# stm32c8t6.net
KiCad netlist of a schematic drawn in Altium Designer
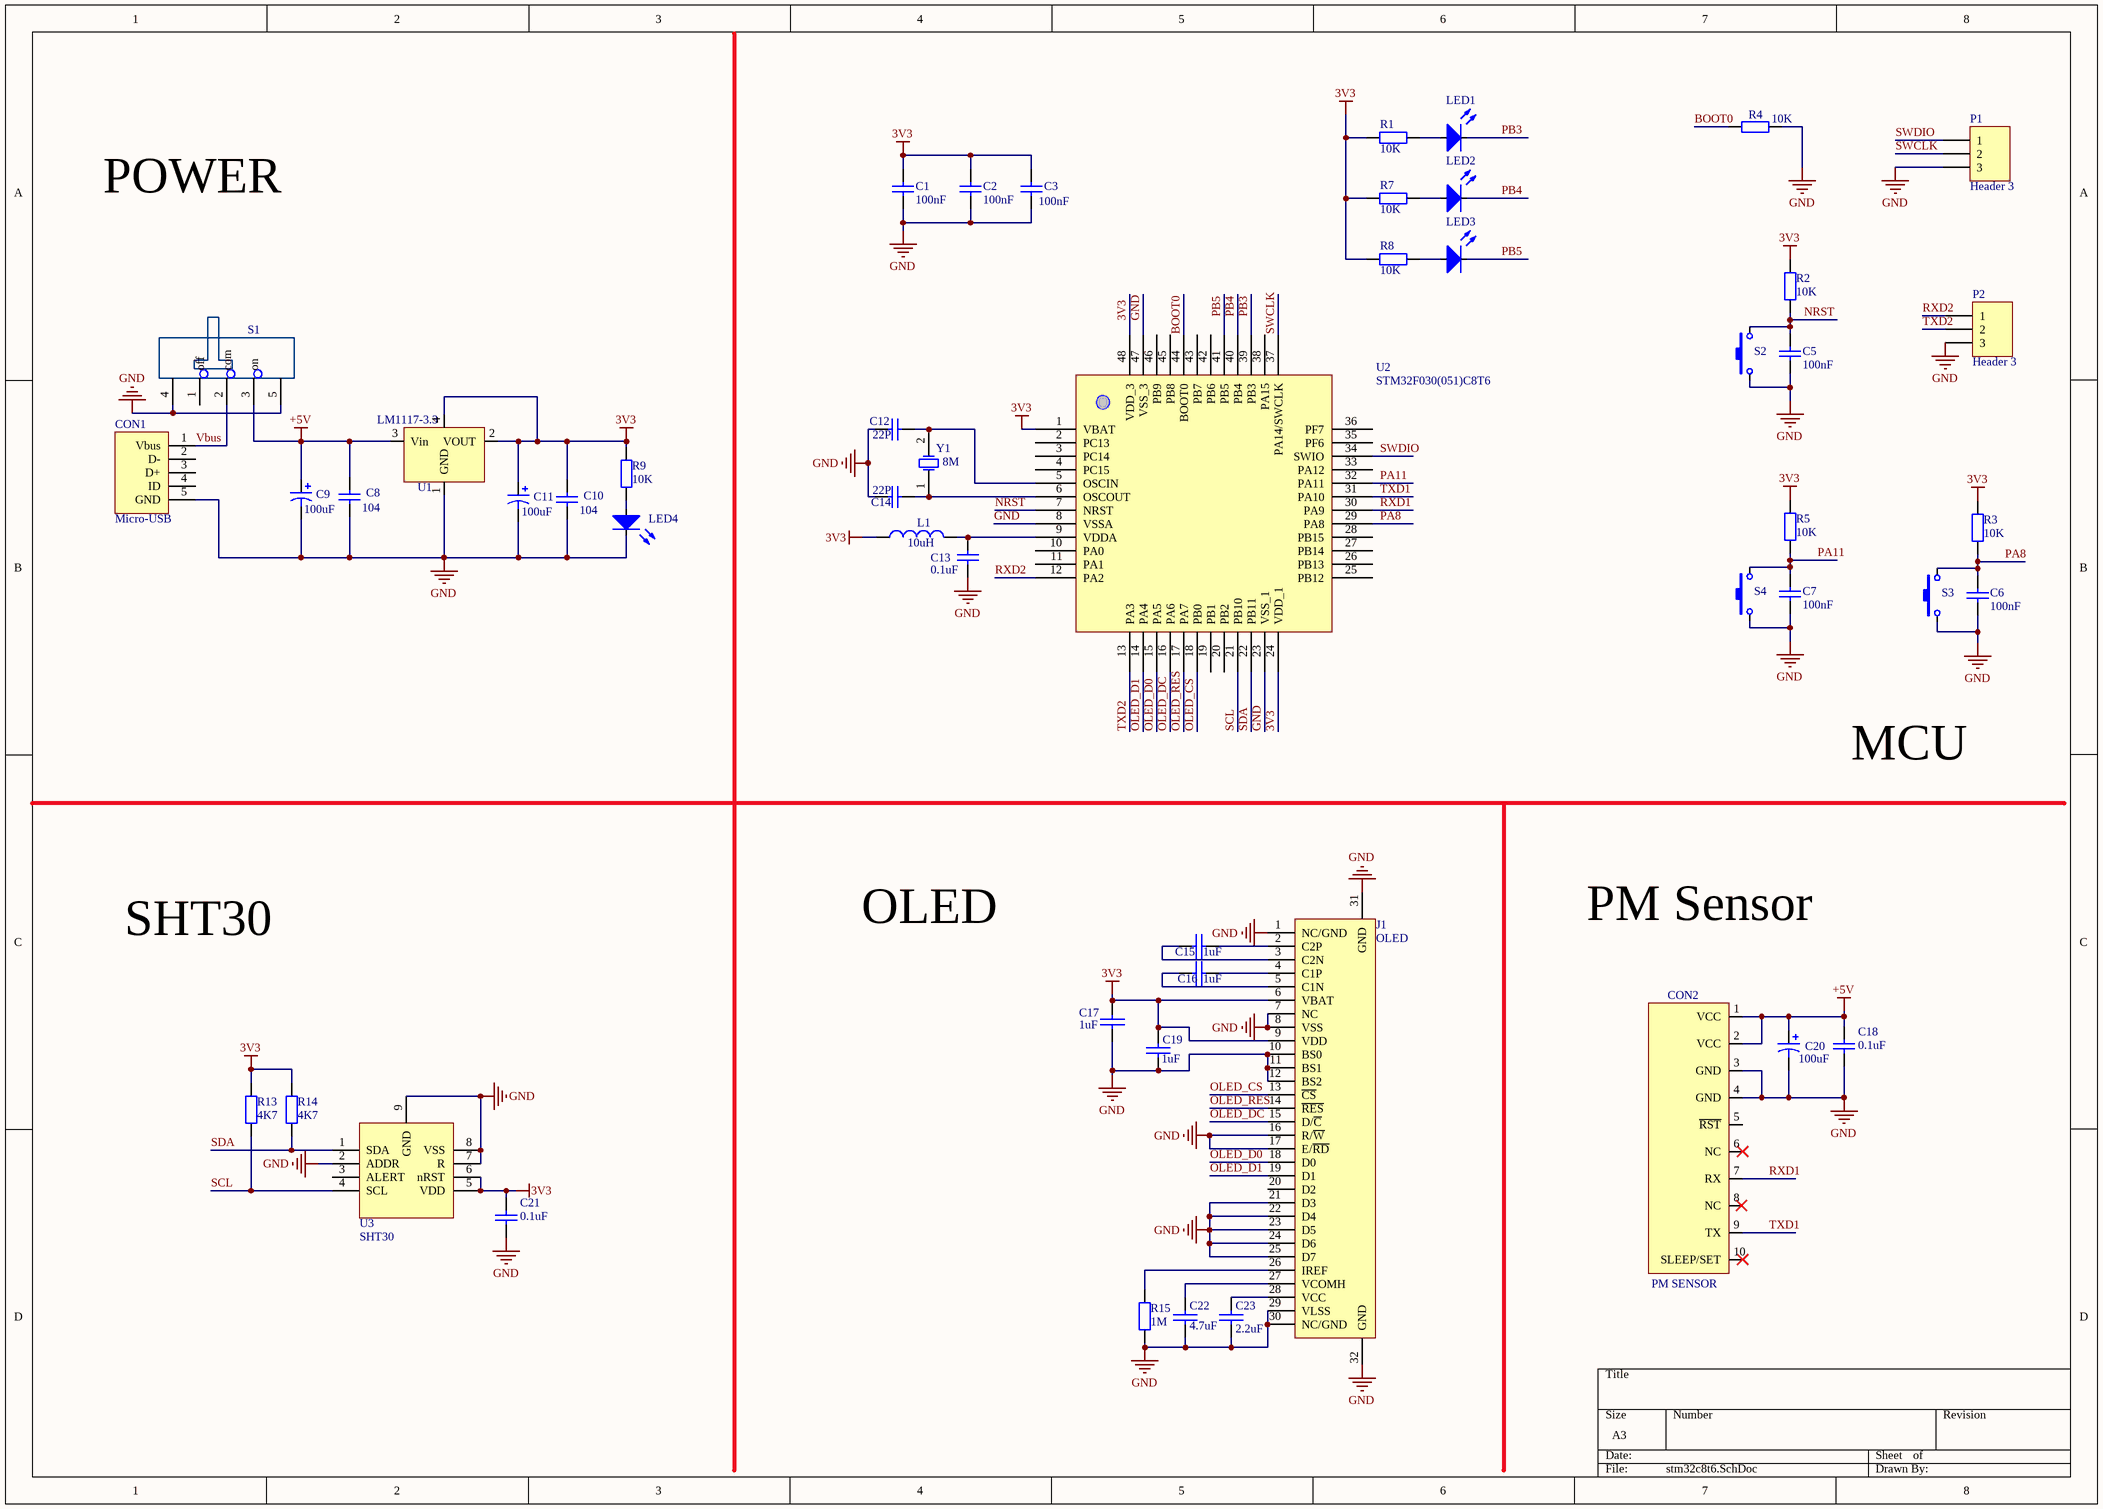
[diagram p0: stm32c8t6.SchDoc]

(export (version "E")
  (design (tool "Eeschema 10.0.6"))
  (components
    (comp (ref "C1")
      (value "100nF")
      (footprint "0603BY")
      (description "Capacitor")
      (fields (field (name "Comment") "Cap") (field (name "PUBLISHER") "Altium Limited"))
      (libsource (lib "stm32c8t6") (part "Cap"))
    )
    (comp (ref "C2")
      (value "100nF")
      (footprint "0603BY")
      (description "Capacitor")
      (fields (field (name "Comment") "Cap") (field (name "PUBLISHER") "Altium Limited"))
      (libsource (lib "stm32c8t6") (part "Cap"))
    )
    (comp (ref "C3")
      (value "100nF")
      (footprint "0603BY")
      (description "Capacitor")
      (fields (field (name "Comment") "Cap") (field (name "PUBLISHER") "Altium Limited"))
      (libsource (lib "stm32c8t6") (part "Cap"))
    )
    (comp (ref "C5")
      (value "100nF")
      (footprint "0603BY")
      (description "Capacitor")
      (fields (field (name "Comment") "Cap") (field (name "PUBLISHER") "Altium Limited"))
      (libsource (lib "stm32c8t6") (part "Cap"))
    )
    (comp (ref "C6")
      (value "100nF")
      (footprint "0603BY")
      (description "Capacitor")
      (fields (field (name "Comment") "Cap") (field (name "PUBLISHER") "Altium Limited"))
      (libsource (lib "stm32c8t6") (part "Cap"))
    )
    (comp (ref "C7")
      (value "100nF")
      (footprint "0603BY")
      (description "Capacitor")
      (fields (field (name "Comment") "Cap") (field (name "PUBLISHER") "Altium Limited"))
      (libsource (lib "stm32c8t6") (part "Cap"))
    )
    (comp (ref "C8")
      (value "104")
      (footprint "0603BY")
      (description "Capacitor")
      (fields (field (name "Comment") "100nF") (field (name "PUBLISHER") "Altium Limited"))
      (libsource (lib "Miscellaneous Devices") (part "Cap"))
    )
    (comp (ref "C9")
      (value "100uF")
      (footprint "C T - TAJB")
      (description "Polarized Capacitor (Radial)")
      (fields (field (name "Comment") "100uF/35V") (field (name "PUBLISHER") "Altium Limited"))
      (libsource (lib "Miscellaneous Devices") (part "Cap Pol1"))
    )
    (comp (ref "C10")
      (value "104")
      (footprint "0603BY")
      (description "Capacitor")
      (fields (field (name "Comment") "100nF") (field (name "PUBLISHER") "Altium Limited"))
      (libsource (lib "Miscellaneous Devices") (part "Cap"))
    )
    (comp (ref "C11")
      (value "100uF")
      (footprint "C T - TAJB")
      (description "Polarized Capacitor (Radial)")
      (fields (field (name "Comment") "100uF/35V") (field (name "PUBLISHER") "Altium Limited"))
      (libsource (lib "Miscellaneous Devices") (part "Cap Pol1"))
    )
    (comp (ref "C12")
      (value "22P")
      (footprint "0603BY")
      (description "Capacitor")
      (fields (field (name "Comment") "Cap") (field (name "PUBLISHER") "Altium Limited"))
      (libsource (lib "stm32c8t6") (part "Cap"))
    )
    (comp (ref "C13")
      (value "0.1uF")
      (footprint "0603BY")
      (description "Capacitor")
      (fields (field (name "Comment") "100nF") (field (name "PUBLISHER") "Altium Limited"))
      (libsource (lib "Miscellaneous Devices") (part "Cap"))
    )
    (comp (ref "C14")
      (value "22P")
      (footprint "0603BY")
      (description "Capacitor")
      (fields (field (name "Comment") "Cap") (field (name "PUBLISHER") "Altium Limited"))
      (libsource (lib "stm32c8t6") (part "Cap"))
    )
    (comp (ref "C15")
      (value "1uF")
      (footprint "0603BY")
      (description "Capacitor")
      (libsource (lib "*") (part "CAP"))
    )
    (comp (ref "C16")
      (value "1uF")
      (footprint "0603BY")
      (description "Capacitor")
      (libsource (lib "*") (part "CAP"))
    )
    (comp (ref "C17")
      (value "1uF")
      (footprint "0603BY")
      (description "Capacitor")
      (libsource (lib "*") (part "CAP"))
    )
    (comp (ref "C18")
      (value "0.1uF")
      (footprint "0603BY")
      (description "Capacitor")
      (fields (field (name "Comment") "100nF") (field (name "PUBLISHER") "Altium Limited"))
      (libsource (lib "Miscellaneous Devices") (part "Cap"))
    )
    (comp (ref "C19")
      (value "1uF")
      (footprint "0603BY")
      (description "Capacitor")
      (libsource (lib "*") (part "CAP"))
    )
    (comp (ref "C20")
      (value "100uF")
      (footprint "C T - TAJB")
      (description "Polarized Capacitor (Radial)")
      (fields (field (name "Comment") "100uF/35V") (field (name "PUBLISHER") "Altium Limited"))
      (libsource (lib "Miscellaneous Devices") (part "Cap Pol1"))
    )
    (comp (ref "C21")
      (value "0.1uF")
      (footprint "0603BY")
      (description "Capacitor")
      (fields (field (name "Comment") "100nF") (field (name "PUBLISHER") "Altium Limited"))
      (libsource (lib "Miscellaneous Devices") (part "Cap"))
    )
    (comp (ref "C22")
      (value "4.7uF")
      (footprint "0603BY")
      (description "Capacitor")
      (libsource (lib "*") (part "CAP"))
    )
    (comp (ref "C23")
      (value "2.2uF")
      (footprint "0603BY")
      (description "Capacitor")
      (libsource (lib "*") (part "CAP"))
    )
    (comp (ref "CON1")
      (value "Micro-USB")
      (footprint "HF00226SA - New")
      (libsource (lib "组网器") (part "Micro-USB"))
    )
    (comp (ref "CON2")
      (value "PM SENSOR")
      (footprint "PM2.5")
      (libsource (lib "PM2.5 检测") (part "PM SENSOR"))
    )
    (comp (ref "J1")
      (value "OLED")
      (footprint "FPC-30P")
      (description "FPC-0.5*30")
      (libsource (lib "stm32c8t6") (part "OLED"))
    )
    (comp (ref "L1")
      (value "10uH")
      (footprint "0805 C")
      (description "HL00079SA")
      (libsource (lib "原理图库") (part "Inductor"))
    )
    (comp (ref "LED1")
      (value "~")
      (footprint "b1206")
      (description "Typical INFRARED GaAs LED")
      (fields (field (name "PUBLISHER") "Altium Limited"))
      (libsource (lib "stm32c8t6") (part "LED0"))
    )
    (comp (ref "LED2")
      (value "~")
      (footprint "b1206")
      (description "Typical INFRARED GaAs LED")
      (fields (field (name "PUBLISHER") "Altium Limited"))
      (libsource (lib "stm32c8t6") (part "LED0"))
    )
    (comp (ref "LED3")
      (value "~")
      (footprint "b1206")
      (description "Typical INFRARED GaAs LED")
      (fields (field (name "PUBLISHER") "Altium Limited"))
      (libsource (lib "stm32c8t6") (part "LED0"))
    )
    (comp (ref "LED4")
      (value "~")
      (footprint "B-0603")
      (description "Typical INFRARED GaAs LED")
      (fields (field (name "PUBLISHER") "Altium Limited"))
      (libsource (lib "stm32c8t6") (part "LED0"))
    )
    (comp (ref "P1")
      (value "Header 3")
      (footprint "HDR1X3")
      (description "Header, 3-Pin")
      (fields (field (name "PUBLISHER") "Altium Limited"))
      (libsource (lib "Miscellaneous Connectors") (part "Header 3"))
    )
    (comp (ref "P2")
      (value "Header 3")
      (footprint "HDR1X3")
      (description "Header, 3-Pin")
      (fields (field (name "PUBLISHER") "Altium Limited"))
      (libsource (lib "Miscellaneous Connectors") (part "Header 3"))
    )
    (comp (ref "R1")
      (value "10K")
      (footprint "0603BY")
      (description "Resistor")
      (fields (field (name "Comment") "Res2") (field (name "PUBLISHER") "Altium Limited"))
      (libsource (lib "") (part "Res2_1"))
    )
    (comp (ref "R2")
      (value "10K")
      (footprint "0603BY")
      (description "Resistor")
      (fields (field (name "Comment") "Res2") (field (name "PUBLISHER") "Altium Limited"))
      (libsource (lib "stm32c8t6") (part "Res2"))
    )
    (comp (ref "R3")
      (value "10K")
      (footprint "0603BY")
      (description "Resistor")
      (fields (field (name "Comment") "Res2") (field (name "PUBLISHER") "Altium Limited"))
      (libsource (lib "stm32c8t6") (part "Res2"))
    )
    (comp (ref "R4")
      (value "10K")
      (footprint "0603BY")
      (description "Resistor")
      (fields (field (name "Comment") "Res2") (field (name "PUBLISHER") "Altium Limited"))
      (libsource (lib "") (part "Res2_1"))
    )
    (comp (ref "R5")
      (value "10K")
      (footprint "0603BY")
      (description "Resistor")
      (fields (field (name "Comment") "Res2") (field (name "PUBLISHER") "Altium Limited"))
      (libsource (lib "stm32c8t6") (part "Res2"))
    )
    (comp (ref "R7")
      (value "10K")
      (footprint "0603BY")
      (description "Resistor")
      (fields (field (name "Comment") "Res2") (field (name "PUBLISHER") "Altium Limited"))
      (libsource (lib "") (part "Res2_1"))
    )
    (comp (ref "R8")
      (value "10K")
      (footprint "0603BY")
      (description "Resistor")
      (fields (field (name "Comment") "Res2") (field (name "PUBLISHER") "Altium Limited"))
      (libsource (lib "") (part "Res2_1"))
    )
    (comp (ref "R9")
      (value "10K")
      (footprint "0603BY")
      (description "Resistor")
      (fields (field (name "Comment") "Res2") (field (name "PUBLISHER") "Altium Limited"))
      (libsource (lib "stm32c8t6") (part "Res2"))
    )
    (comp (ref "R13")
      (value "4K7")
      (footprint "0603BY")
      (description "Resistor")
      (fields (field (name "Comment") "Res2") (field (name "PUBLISHER") "Altium Limited"))
      (libsource (lib "stm32c8t6") (part "Res2"))
    )
    (comp (ref "R14")
      (value "4K7")
      (footprint "0603BY")
      (description "Resistor")
      (fields (field (name "Comment") "Res2") (field (name "PUBLISHER") "Altium Limited"))
      (libsource (lib "stm32c8t6") (part "Res2"))
    )
    (comp (ref "R15")
      (value "1M")
      (footprint "0603BY")
      (description "Resistor")
      (fields (field (name "Comment") "Res2") (field (name "PUBLISHER") "Altium Limited"))
      (libsource (lib "stm32c8t6") (part "Res2"))
    )
    (comp (ref "S1")
      (value "SW-SPST")
      (footprint "SS-12F44")
      (description "Single-Pole, Single-Throw Switch")
      (fields (field (name "PUBLISHER") "Altium Limited"))
      (libsource (lib "组网器") (part "SW-SPST"))
    )
    (comp (ref "S2")
      (value "SW-PB")
      (footprint "HQ1SA")
      (description "Switch")
      (fields (field (name "PUBLISHER") "Altium Limited"))
      (libsource (lib "stm32c8t6") (part "SW-PB"))
    )
    (comp (ref "S3")
      (value "SW-PB")
      (footprint "HQ1SA")
      (description "Switch")
      (fields (field (name "PUBLISHER") "Altium Limited"))
      (libsource (lib "stm32c8t6") (part "SW-PB"))
    )
    (comp (ref "S4")
      (value "SW-PB")
      (footprint "HQ1SA")
      (description "Switch")
      (fields (field (name "PUBLISHER") "Altium Limited"))
      (libsource (lib "stm32c8t6") (part "SW-PB"))
    )
    (comp (ref "U1") (value "LM1117-3.3") (footprint "SOT223") (libsource (lib "PM 2.5") (part "LM1117")))
    (comp (ref "U2")
      (value "STM32F030(051)C8T6")
      (footprint "stm32f103_48")
      (libsource (lib "stm32c8t6") (part "STM32F030C8T6"))
    )
    (comp (ref "U3") (value "SHT30") (footprint "SHT30") (libsource (lib "stm32c8t6") (part "SHT30")))
    (comp (ref "Y1")
      (value "8M")
      (footprint "XTAL-DIP")
      (description "Crystal Oscillator")
      (fields (field (name "PUBLISHER") "Altium Limited"))
      (libsource (lib "Miscellaneous Devices") (part "XTAL"))
    )
  )
  (nets
    (net (code "1") (name "+5V") (class "Default")
      (node (ref "C18") (pin "2") (pinfunction "2_2") (pintype "passive"))
      (node (ref "C20") (pin "1") (pinfunction "1_1") (pintype "passive"))
      (node (ref "C8") (pin "1") (pinfunction "1_1") (pintype "passive"))
      (node (ref "C9") (pin "1") (pinfunction "1_1") (pintype "passive"))
      (node (ref "CON2") (pin "1") (pinfunction "VCC_1") (pintype "passive"))
      (node (ref "CON2") (pin "2") (pinfunction "VCC_2") (pintype "passive"))
      (node (ref "S1") (pin "3") (pinfunction "on_3") (pintype "passive"))
      (node (ref "U1") (pin "3") (pinfunction "Vin_3") (pintype "passive"))
    )
    (net (code "2") (name "/BOOT0") (class "Default")
      (node (ref "R4") (pin "1") (pinfunction "1_1") (pintype "passive"))
      (node (ref "U2") (pin "44") (pinfunction "BOOT0_44") (pintype "passive"))
    )
    (net (code "3") (name "/NRST") (class "Default")
      (node (ref "C5") (pin "1") (pinfunction "1_1") (pintype "passive"))
      (node (ref "R2") (pin "1") (pinfunction "1_1") (pintype "passive"))
      (node (ref "S2") (pin "2") (pinfunction "2_2") (pintype "passive"))
      (node (ref "U2") (pin "7") (pinfunction "NRST_7") (pintype "passive"))
    )
    (net (code "4") (name "/OLED_CS") (class "Default")
      (node (ref "J1") (pin "13") (pinfunction "~{CS}_13") (pintype "passive"))
      (node (ref "U2") (pin "18") (pinfunction "PB0_18") (pintype "passive"))
    )
    (net (code "5") (name "/OLED_D0") (class "Default")
      (node (ref "J1") (pin "18") (pinfunction "D0_18") (pintype "passive"))
      (node (ref "U2") (pin "15") (pinfunction "PA5_15") (pintype "passive"))
    )
    (net (code "6") (name "/OLED_D1") (class "Default")
      (node (ref "J1") (pin "19") (pinfunction "D1_19") (pintype "passive"))
      (node (ref "U2") (pin "14") (pinfunction "PA4_14") (pintype "passive"))
    )
    (net (code "7") (name "/OLED_DC") (class "Default")
      (node (ref "J1") (pin "15") (pinfunction "D/~{C}_15") (pintype "passive"))
      (node (ref "U2") (pin "16") (pinfunction "PA6_16") (pintype "passive"))
    )
    (net (code "8") (name "/OLED_RES") (class "Default")
      (node (ref "J1") (pin "14") (pinfunction "~{RES}_14") (pintype "passive"))
      (node (ref "U2") (pin "17") (pinfunction "PA7_17") (pintype "passive"))
    )
    (net (code "9") (name "/PA8") (class "Default")
      (node (ref "C6") (pin "1") (pinfunction "1_1") (pintype "passive"))
      (node (ref "R3") (pin "1") (pinfunction "1_1") (pintype "passive"))
      (node (ref "S3") (pin "2") (pinfunction "2_2") (pintype "passive"))
      (node (ref "U2") (pin "29") (pinfunction "PA8_29") (pintype "passive"))
    )
    (net (code "10") (name "/PA11") (class "Default")
      (node (ref "C7") (pin "1") (pinfunction "1_1") (pintype "passive"))
      (node (ref "R5") (pin "1") (pinfunction "1_1") (pintype "passive"))
      (node (ref "S4") (pin "2") (pinfunction "2_2") (pintype "passive"))
      (node (ref "U2") (pin "32") (pinfunction "PA11_32") (pintype "passive"))
    )
    (net (code "11") (name "/PB3") (class "Default")
      (node (ref "LED1") (pin "2") (pinfunction "K_2") (pintype "passive"))
      (node (ref "U2") (pin "39") (pinfunction "PB3_39") (pintype "passive"))
    )
    (net (code "12") (name "/PB4") (class "Default")
      (node (ref "LED2") (pin "2") (pinfunction "K_2") (pintype "passive"))
      (node (ref "U2") (pin "40") (pinfunction "PB4_40") (pintype "passive"))
    )
    (net (code "13") (name "/PB5") (class "Default")
      (node (ref "LED3") (pin "2") (pinfunction "K_2") (pintype "passive"))
      (node (ref "U2") (pin "41") (pinfunction "PB5_41") (pintype "passive"))
    )
    (net (code "14") (name "/RXD1") (class "Default")
      (node (ref "CON2") (pin "7") (pinfunction "RX_7") (pintype "passive"))
      (node (ref "U2") (pin "30") (pinfunction "PA9_30") (pintype "passive"))
    )
    (net (code "15") (name "/RXD2") (class "Default")
      (node (ref "P2") (pin "1") (pinfunction "1_1") (pintype "passive"))
      (node (ref "U2") (pin "12") (pinfunction "PA2_12") (pintype "passive"))
    )
    (net (code "16") (name "/SCL") (class "Default")
      (node (ref "R13") (pin "1") (pinfunction "1_1") (pintype "passive"))
      (node (ref "U2") (pin "21") (pinfunction "PB10_21") (pintype "passive"))
      (node (ref "U3") (pin "4") (pinfunction "SCL_4") (pintype "passive"))
    )
    (net (code "17") (name "/SDA") (class "Default")
      (node (ref "R14") (pin "1") (pinfunction "1_1") (pintype "passive"))
      (node (ref "U2") (pin "22") (pinfunction "PB11_22") (pintype "passive"))
      (node (ref "U3") (pin "1") (pinfunction "SDA_1") (pintype "passive"))
    )
    (net (code "18") (name "/SWCLK") (class "Default")
      (node (ref "P1") (pin "2") (pinfunction "2_2") (pintype "passive"))
      (node (ref "U2") (pin "37") (pinfunction "PA14/SWCLK_37") (pintype "passive"))
    )
    (net (code "19") (name "/SWDIO") (class "Default")
      (node (ref "P1") (pin "1") (pinfunction "1_1") (pintype "passive"))
      (node (ref "U2") (pin "34") (pinfunction "SWIO_34") (pintype "passive"))
    )
    (net (code "20") (name "/TXD1") (class "Default")
      (node (ref "CON2") (pin "9") (pinfunction "TX_9") (pintype "passive"))
      (node (ref "U2") (pin "31") (pinfunction "PA10_31") (pintype "passive"))
    )
    (net (code "21") (name "/TXD2") (class "Default")
      (node (ref "P2") (pin "2") (pinfunction "2_2") (pintype "passive"))
      (node (ref "U2") (pin "13") (pinfunction "PA3_13") (pintype "passive"))
    )
    (net (code "22") (name "/Vbus") (class "Default")
      (node (ref "CON1") (pin "1") (pinfunction "Vbus_1") (pintype "passive"))
      (node (ref "S1") (pin "2") (pinfunction "com_2") (pintype "passive"))
    )
    (net (code "23") (name "3V3") (class "Default")
      (node (ref "C1") (pin "1") (pinfunction "1_1") (pintype "passive"))
      (node (ref "C10") (pin "1") (pinfunction "1_1") (pintype "passive"))
      (node (ref "C11") (pin "1") (pinfunction "1_1") (pintype "passive"))
      (node (ref "C17") (pin "2") (pinfunction "2_2") (pintype "passive"))
      (node (ref "C19") (pin "2") (pinfunction "2_2") (pintype "passive"))
      (node (ref "C2") (pin "1") (pinfunction "1_1") (pintype "passive"))
      (node (ref "C21") (pin "2") (pinfunction "2_2") (pintype "passive"))
      (node (ref "C3") (pin "2") (pinfunction "2_2") (pintype "passive"))
      (node (ref "J1") (pin "6") (pinfunction "VBAT_6") (pintype "passive"))
      (node (ref "J1") (pin "9") (pinfunction "VDD_9") (pintype "passive"))
      (node (ref "L1") (pin "2") (pinfunction "2_2") (pintype "passive"))
      (node (ref "R1") (pin "1") (pinfunction "1_1") (pintype "passive"))
      (node (ref "R13") (pin "2") (pinfunction "2_2") (pintype "passive"))
      (node (ref "R14") (pin "2") (pinfunction "2_2") (pintype "passive"))
      (node (ref "R2") (pin "2") (pinfunction "2_2") (pintype "passive"))
      (node (ref "R3") (pin "2") (pinfunction "2_2") (pintype "passive"))
      (node (ref "R5") (pin "2") (pinfunction "2_2") (pintype "passive"))
      (node (ref "R7") (pin "1") (pinfunction "1_1") (pintype "passive"))
      (node (ref "R8") (pin "1") (pinfunction "1_1") (pintype "passive"))
      (node (ref "R9") (pin "2") (pinfunction "2_2") (pintype "passive"))
      (node (ref "U1") (pin "2") (pinfunction "VOUT_2") (pintype "passive"))
      (node (ref "U1") (pin "4") (pinfunction "VOUT_4") (pintype "passive"))
      (node (ref "U2") (pin "1") (pinfunction "VBAT_1") (pintype "passive"))
      (node (ref "U2") (pin "24") (pinfunction "VDD_1_24") (pintype "passive"))
      (node (ref "U2") (pin "48") (pinfunction "VDD_3_48") (pintype "passive"))
      (node (ref "U3") (pin "5") (pinfunction "VDD_5") (pintype "passive"))
      (node (ref "U3") (pin "6") (pinfunction "nRST_6") (pintype "passive"))
    )
    (net (code "24") (name "GND") (class "Default")
      (node (ref "C1") (pin "2") (pinfunction "2_2") (pintype "passive"))
      (node (ref "C10") (pin "2") (pinfunction "2_2") (pintype "passive"))
      (node (ref "C11") (pin "2") (pinfunction "2_2") (pintype "passive"))
      (node (ref "C12") (pin "2") (pinfunction "2_2") (pintype "passive"))
      (node (ref "C13") (pin "1") (pinfunction "1_1") (pintype "passive"))
      (node (ref "C14") (pin "2") (pinfunction "2_2") (pintype "passive"))
      (node (ref "C17") (pin "1") (pinfunction "1_1") (pintype "passive"))
      (node (ref "C18") (pin "1") (pinfunction "1_1") (pintype "passive"))
      (node (ref "C19") (pin "1") (pinfunction "1_1") (pintype "passive"))
      (node (ref "C2") (pin "2") (pinfunction "2_2") (pintype "passive"))
      (node (ref "C20") (pin "2") (pinfunction "2_2") (pintype "passive"))
      (node (ref "C21") (pin "1") (pinfunction "1_1") (pintype "passive"))
      (node (ref "C22") (pin "2") (pinfunction "2_2") (pintype "passive"))
      (node (ref "C23") (pin "2") (pinfunction "2_2") (pintype "passive"))
      (node (ref "C3") (pin "1") (pinfunction "1_1") (pintype "passive"))
      (node (ref "C5") (pin "2") (pinfunction "2_2") (pintype "passive"))
      (node (ref "C6") (pin "2") (pinfunction "2_2") (pintype "passive"))
      (node (ref "C7") (pin "2") (pinfunction "2_2") (pintype "passive"))
      (node (ref "C8") (pin "2") (pinfunction "2_2") (pintype "passive"))
      (node (ref "C9") (pin "2") (pinfunction "2_2") (pintype "passive"))
      (node (ref "CON1") (pin "5") (pinfunction "GND_5") (pintype "passive"))
      (node (ref "CON2") (pin "3") (pinfunction "GND_3") (pintype "passive"))
      (node (ref "CON2") (pin "4") (pinfunction "GND_4") (pintype "passive"))
      (node (ref "J1") (pin "1") (pinfunction "NC/GND_1") (pintype "passive"))
      (node (ref "J1") (pin "10") (pinfunction "BS0_10") (pintype "passive"))
      (node (ref "J1") (pin "11") (pinfunction "BS1_11") (pintype "passive"))
      (node (ref "J1") (pin "12") (pinfunction "BS2_12") (pintype "passive"))
      (node (ref "J1") (pin "16") (pinfunction "R/~{W}_16") (pintype "passive"))
      (node (ref "J1") (pin "17") (pinfunction "E/~{RD}_17") (pintype "passive"))
      (node (ref "J1") (pin "21") (pinfunction "D3_21") (pintype "passive"))
      (node (ref "J1") (pin "22") (pinfunction "D4_22") (pintype "passive"))
      (node (ref "J1") (pin "23") (pinfunction "D5_23") (pintype "passive"))
      (node (ref "J1") (pin "24") (pinfunction "D6_24") (pintype "passive"))
      (node (ref "J1") (pin "25") (pinfunction "D7_25") (pintype "passive"))
      (node (ref "J1") (pin "29") (pinfunction "VLSS_29") (pintype "passive"))
      (node (ref "J1") (pin "30") (pinfunction "NC/GND_30") (pintype "passive"))
      (node (ref "J1") (pin "31") (pinfunction "GND_31") (pintype "passive"))
      (node (ref "J1") (pin "32") (pinfunction "GND_32") (pintype "passive"))
      (node (ref "J1") (pin "7") (pinfunction "NC_7") (pintype "passive"))
      (node (ref "J1") (pin "8") (pinfunction "VSS_8") (pintype "passive"))
      (node (ref "LED4") (pin "2") (pinfunction "K_2") (pintype "passive"))
      (node (ref "P1") (pin "3") (pinfunction "3_3") (pintype "passive"))
      (node (ref "P2") (pin "3") (pinfunction "3_3") (pintype "passive"))
      (node (ref "R15") (pin "1") (pinfunction "1_1") (pintype "passive"))
      (node (ref "R4") (pin "2") (pinfunction "2_2") (pintype "passive"))
      (node (ref "S1") (pin "4") (pinfunction "4_4") (pintype "passive"))
      (node (ref "S1") (pin "5") (pinfunction "5_5") (pintype "passive"))
      (node (ref "S2") (pin "1") (pinfunction "1_1") (pintype "passive"))
      (node (ref "S3") (pin "1") (pinfunction "1_1") (pintype "passive"))
      (node (ref "S4") (pin "1") (pinfunction "1_1") (pintype "passive"))
      (node (ref "U1") (pin "1") (pinfunction "GND_1") (pintype "passive"))
      (node (ref "U2") (pin "23") (pinfunction "VSS_1_23") (pintype "passive"))
      (node (ref "U2") (pin "47") (pinfunction "VSS_3_47") (pintype "passive"))
      (node (ref "U2") (pin "8") (pinfunction "VSSA_8") (pintype "passive"))
      (node (ref "U3") (pin "2") (pinfunction "ADDR_2") (pintype "passive"))
      (node (ref "U3") (pin "7") (pinfunction "R_7") (pintype "passive"))
      (node (ref "U3") (pin "8") (pinfunction "VSS_8") (pintype "passive"))
      (node (ref "U3") (pin "9") (pinfunction "GND_9") (pintype "passive"))
    )
    (net (code "25") (name "Net-(J1-C1N)") (class "Default")
      (node (ref "C16") (pin "1") (pinfunction "1_1") (pintype "passive"))
      (node (ref "J1") (pin "5") (pinfunction "C1N_5") (pintype "passive"))
    )
    (net (code "26") (name "Net-(J1-C1P)") (class "Default")
      (node (ref "C16") (pin "2") (pinfunction "2_2") (pintype "passive"))
      (node (ref "J1") (pin "4") (pinfunction "C1P_4") (pintype "passive"))
    )
    (net (code "27") (name "Net-(J1-C2N)") (class "Default")
      (node (ref "C15") (pin "1") (pinfunction "1_1") (pintype "passive"))
      (node (ref "J1") (pin "3") (pinfunction "C2N_3") (pintype "passive"))
    )
    (net (code "28") (name "Net-(J1-C2P)") (class "Default")
      (node (ref "C15") (pin "2") (pinfunction "2_2") (pintype "passive"))
      (node (ref "J1") (pin "2") (pinfunction "C2P_2") (pintype "passive"))
    )
    (net (code "29") (name "Net-(J1-IREF)") (class "Default")
      (node (ref "J1") (pin "26") (pinfunction "IREF_26") (pintype "passive"))
      (node (ref "R15") (pin "2") (pinfunction "2_2") (pintype "passive"))
    )
    (net (code "30") (name "Net-(J1-VCC)") (class "Default")
      (node (ref "C23") (pin "1") (pinfunction "1_1") (pintype "passive"))
      (node (ref "J1") (pin "28") (pinfunction "VCC_28") (pintype "passive"))
    )
    (net (code "31") (name "Net-(J1-VCOMH)") (class "Default")
      (node (ref "C22") (pin "1") (pinfunction "1_1") (pintype "passive"))
      (node (ref "J1") (pin "27") (pinfunction "VCOMH_27") (pintype "passive"))
    )
    (net (code "32") (name "Net-(LED1-A)") (class "Default")
      (node (ref "LED1") (pin "1") (pinfunction "A_1") (pintype "passive"))
      (node (ref "R1") (pin "2") (pinfunction "2_2") (pintype "passive"))
    )
    (net (code "33") (name "Net-(LED2-A)") (class "Default")
      (node (ref "LED2") (pin "1") (pinfunction "A_1") (pintype "passive"))
      (node (ref "R7") (pin "2") (pinfunction "2_2") (pintype "passive"))
    )
    (net (code "34") (name "Net-(LED3-A)") (class "Default")
      (node (ref "LED3") (pin "1") (pinfunction "A_1") (pintype "passive"))
      (node (ref "R8") (pin "2") (pinfunction "2_2") (pintype "passive"))
    )
    (net (code "35") (name "Net-(LED4-A)") (class "Default")
      (node (ref "LED4") (pin "1") (pinfunction "A_1") (pintype "passive"))
      (node (ref "R9") (pin "1") (pinfunction "1_1") (pintype "passive"))
    )
    (net (code "36") (name "Net-(U2-OSCIN)") (class "Default")
      (node (ref "C12") (pin "1") (pinfunction "1_1") (pintype "passive"))
      (node (ref "U2") (pin "5") (pinfunction "OSCIN_5") (pintype "passive"))
      (node (ref "Y1") (pin "2") (pinfunction "OSC2_2") (pintype "passive"))
    )
    (net (code "37") (name "Net-(U2-OSCOUT)") (class "Default")
      (node (ref "C14") (pin "1") (pinfunction "1_1") (pintype "passive"))
      (node (ref "U2") (pin "6") (pinfunction "OSCOUT_6") (pintype "passive"))
      (node (ref "Y1") (pin "1") (pinfunction "OSC1_1") (pintype "passive"))
    )
    (net (code "38") (name "Net-(U2-VDDA)") (class "Default")
      (node (ref "C13") (pin "2") (pinfunction "2_2") (pintype "passive"))
      (node (ref "L1") (pin "1") (pinfunction "1_1") (pintype "passive"))
      (node (ref "U2") (pin "9") (pinfunction "VDDA_9") (pintype "passive"))
    )
    (net (code "39") (name "unconnected-(CON1-D+-Pad3)") (class "Default")
      (node (ref "CON1") (pin "3") (pinfunction "D+_3") (pintype "passive"))
    )
    (net (code "40") (name "unconnected-(CON1-D--Pad2)") (class "Default")
      (node (ref "CON1") (pin "2") (pinfunction "D-_2") (pintype "passive"))
    )
    (net (code "41") (name "unconnected-(CON1-ID-Pad4)") (class "Default")
      (node (ref "CON1") (pin "4") (pinfunction "ID_4") (pintype "passive"))
    )
    (net (code "42") (name "unconnected-(CON2-NC-Pad6)") (class "Default")
      (node (ref "CON2") (pin "6") (pinfunction "NC_6") (pintype "passive+no_connect"))
    )
    (net (code "43") (name "unconnected-(CON2-NC-Pad8)") (class "Default")
      (node (ref "CON2") (pin "8") (pinfunction "NC_8") (pintype "passive"))
    )
    (net (code "44") (name "unconnected-(CON2-SLEEP{slash}SET-Pad10)") (class "Default")
      (node (ref "CON2") (pin "10") (pinfunction "SLEEP/SET_10") (pintype "passive+no_connect"))
    )
    (net (code "45") (name "unconnected-(CON2-~{RST}-Pad5)") (class "Default")
      (node (ref "CON2") (pin "5") (pinfunction "~{RST}_5") (pintype "passive"))
    )
    (net (code "46") (name "unconnected-(J1-D2-Pad20)") (class "Default")
      (node (ref "J1") (pin "20") (pinfunction "D2_20") (pintype "passive"))
    )
    (net (code "47") (name "unconnected-(S1-off-Pad1)") (class "Default")
      (node (ref "S1") (pin "1") (pinfunction "off_1") (pintype "passive"))
    )
    (net (code "48") (name "unconnected-(U2-PA0-Pad10)") (class "Default")
      (node (ref "U2") (pin "10") (pinfunction "PA0_10") (pintype "passive"))
    )
    (net (code "49") (name "unconnected-(U2-PA1-Pad11)") (class "Default")
      (node (ref "U2") (pin "11") (pinfunction "PA1_11") (pintype "passive"))
    )
    (net (code "50") (name "unconnected-(U2-PA12-Pad33)") (class "Default")
      (node (ref "U2") (pin "33") (pinfunction "PA12_33") (pintype "passive"))
    )
    (net (code "51") (name "unconnected-(U2-PA15-Pad38)") (class "Default")
      (node (ref "U2") (pin "38") (pinfunction "PA15_38") (pintype "passive"))
    )
    (net (code "52") (name "unconnected-(U2-PB1-Pad19)") (class "Default")
      (node (ref "U2") (pin "19") (pinfunction "PB1_19") (pintype "passive"))
    )
    (net (code "53") (name "unconnected-(U2-PB2-Pad20)") (class "Default")
      (node (ref "U2") (pin "20") (pinfunction "PB2_20") (pintype "passive"))
    )
    (net (code "54") (name "unconnected-(U2-PB6-Pad42)") (class "Default")
      (node (ref "U2") (pin "42") (pinfunction "PB6_42") (pintype "passive"))
    )
    (net (code "55") (name "unconnected-(U2-PB7-Pad43)") (class "Default")
      (node (ref "U2") (pin "43") (pinfunction "PB7_43") (pintype "passive"))
    )
    (net (code "56") (name "unconnected-(U2-PB8-Pad45)") (class "Default")
      (node (ref "U2") (pin "45") (pinfunction "PB8_45") (pintype "passive"))
    )
    (net (code "57") (name "unconnected-(U2-PB9-Pad46)") (class "Default")
      (node (ref "U2") (pin "46") (pinfunction "PB9_46") (pintype "passive"))
    )
    (net (code "58") (name "unconnected-(U2-PB12-Pad25)") (class "Default")
      (node (ref "U2") (pin "25") (pinfunction "PB12_25") (pintype "passive"))
    )
    (net (code "59") (name "unconnected-(U2-PB13-Pad26)") (class "Default")
      (node (ref "U2") (pin "26") (pinfunction "PB13_26") (pintype "passive"))
    )
    (net (code "60") (name "unconnected-(U2-PB14-Pad27)") (class "Default")
      (node (ref "U2") (pin "27") (pinfunction "PB14_27") (pintype "passive"))
    )
    (net (code "61") (name "unconnected-(U2-PB15-Pad28)") (class "Default")
      (node (ref "U2") (pin "28") (pinfunction "PB15_28") (pintype "passive"))
    )
    (net (code "62") (name "unconnected-(U2-PC13-Pad2)") (class "Default")
      (node (ref "U2") (pin "2") (pinfunction "PC13_2") (pintype "passive"))
    )
    (net (code "63") (name "unconnected-(U2-PC14-Pad3)") (class "Default")
      (node (ref "U2") (pin "3") (pinfunction "PC14_3") (pintype "passive"))
    )
    (net (code "64") (name "unconnected-(U2-PC15-Pad4)") (class "Default")
      (node (ref "U2") (pin "4") (pinfunction "PC15_4") (pintype "passive"))
    )
    (net (code "65") (name "unconnected-(U2-PF6-Pad35)") (class "Default")
      (node (ref "U2") (pin "35") (pinfunction "PF6_35") (pintype "passive"))
    )
    (net (code "66") (name "unconnected-(U2-PF7-Pad36)") (class "Default")
      (node (ref "U2") (pin "36") (pinfunction "PF7_36") (pintype "passive"))
    )
    (net (code "67") (name "unconnected-(U3-ALERT-Pad3)") (class "Default")
      (node (ref "U3") (pin "3") (pinfunction "ALERT_3") (pintype "passive"))
    )
  )
)
